# BLE_--_HM-10_--_Carduino_Breakout_v1_0_2.net
KiCad netlist of a schematic drawn in EAGLE
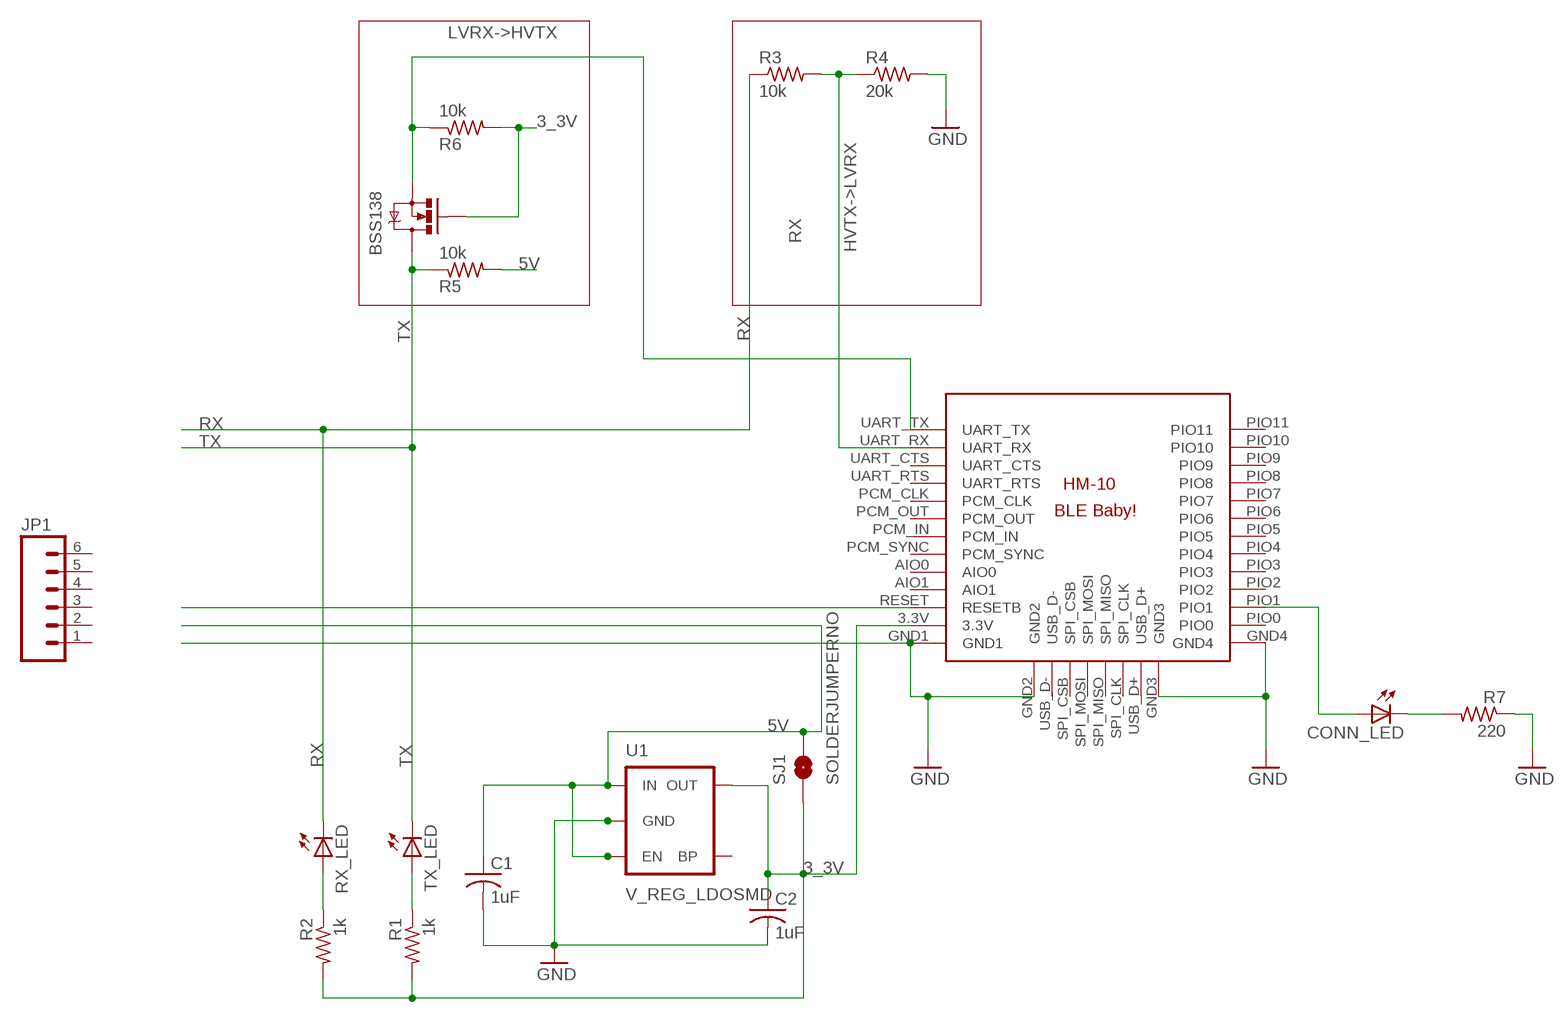
[diagram p0: schematic, sheet 1]

(export (version "E")
  (design (tool "Eeschema 10.0.6"))
  (components
    (comp (ref "BSS138")
      (value "MOSFET-NCHANNELSMD")
      (footprint "eagle-import:SOT23-3")
      (libsource (lib "eagle-import") (part "MOSFET-NCHANNELSMD"))
    )
    (comp (ref "C1")
      (value "1uF")
      (footprint "eagle-import:C0805K")
      (libsource (lib "eagle-import") (part "C-USC0805K"))
    )
    (comp (ref "C2")
      (value "1uF")
      (footprint "eagle-import:C0805K")
      (libsource (lib "eagle-import") (part "C-USC0805K"))
    )
    (comp (ref "CONN_LED")
      (value "LED0603")
      (footprint "eagle-import:LED-0603")
      (libsource (lib "eagle-import") (part "LED0603"))
    )
    (comp (ref "JP1")
      (value "M06SIP")
      (footprint "eagle-import:1X06")
      (libsource (lib "eagle-import") (part "M06SIP"))
    )
    (comp (ref "R1")
      (value "1k")
      (footprint "eagle-import:M0805")
      (libsource (lib "eagle-import") (part "R-US_M0805"))
    )
    (comp (ref "R2")
      (value "1k")
      (footprint "eagle-import:M0805")
      (libsource (lib "eagle-import") (part "R-US_M0805"))
    )
    (comp (ref "R3")
      (value "10k")
      (footprint "eagle-import:M0805")
      (libsource (lib "eagle-import") (part "R-US_M0805"))
    )
    (comp (ref "R4")
      (value "20k")
      (footprint "eagle-import:M0805")
      (libsource (lib "eagle-import") (part "R-US_M0805"))
    )
    (comp (ref "R5")
      (value "10k")
      (footprint "eagle-import:M0805")
      (libsource (lib "eagle-import") (part "R-US_M0805"))
    )
    (comp (ref "R6")
      (value "10k")
      (footprint "eagle-import:M0805")
      (libsource (lib "eagle-import") (part "R-US_M0805"))
    )
    (comp (ref "R7")
      (value "220")
      (footprint "eagle-import:M0805")
      (libsource (lib "eagle-import") (part "R-US_M0805"))
    )
    (comp (ref "RX_LED")
      (value "LED0603")
      (footprint "eagle-import:LED-0603")
      (libsource (lib "eagle-import") (part "LED0603"))
    )
    (comp (ref "SJ1")
      (value "SOLDERJUMPERNO")
      (footprint "eagle-import:SJ_2S-NO")
      (libsource (lib "eagle-import") (part "SOLDERJUMPERNO"))
    )
    (comp (ref "TX_LED")
      (value "LED0603")
      (footprint "eagle-import:LED-0603")
      (libsource (lib "eagle-import") (part "LED0603"))
    )
    (comp (ref "U$1")
      (value "BLE-HM-10")
      (footprint "eagle-import:BLE-HM-10")
      (libsource (lib "eagle-import") (part "BLE-HM-10"))
    )
    (comp (ref "U1")
      (value "V_REG_LDOSMD")
      (footprint "eagle-import:SOT23-5")
      (libsource (lib "eagle-import") (part "V_REG_LDOSMD"))
    )
  )
  (nets
    (net (code "1") (name "/3_3V") (class "Default")
      (node (ref "BSS138") (pin "1") (pinfunction "G_1") (pintype "passive"))
      (node (ref "C2") (pin "1") (pinfunction "1_1") (pintype "passive"))
      (node (ref "R1") (pin "2") (pinfunction "2_2") (pintype "passive"))
      (node (ref "R2") (pin "2") (pinfunction "2_2") (pintype "passive"))
      (node (ref "R6") (pin "2") (pinfunction "2_2") (pintype "passive"))
      (node (ref "SJ1") (pin "1") (pinfunction "1_1") (pintype "passive"))
      (node (ref "U$1") (pin "3.3V") (pinfunction "3.3V_3.3V") (pintype "bidirectional"))
      (node (ref "U1") (pin "5") (pinfunction "OUT_5") (pintype "passive"))
    )
    (net (code "2") (name "/5V") (class "Default")
      (node (ref "C1") (pin "1") (pinfunction "1_1") (pintype "passive"))
      (node (ref "R5") (pin "2") (pinfunction "2_2") (pintype "passive"))
      (node (ref "SJ1") (pin "2") (pinfunction "2_2") (pintype "passive"))
      (node (ref "U1") (pin "1") (pinfunction "IN_1") (pintype "input"))
      (node (ref "U1") (pin "3") (pinfunction "EN_3") (pintype "input"))
    )
    (net (code "3") (name "/HVTX->LVRX") (class "Default")
      (node (ref "R3") (pin "2") (pinfunction "2_2") (pintype "passive"))
      (node (ref "R4") (pin "1") (pinfunction "1_1") (pintype "passive"))
      (node (ref "U$1") (pin "UART_RX") (pinfunction "UART_RX_UART_RX") (pintype "bidirectional"))
    )
    (net (code "4") (name "/LVRX->HVTX") (class "Default")
      (node (ref "BSS138") (pin "2") (pinfunction "S_2") (pintype "passive"))
      (node (ref "R6") (pin "1") (pinfunction "1_1") (pintype "passive"))
      (node (ref "U$1") (pin "UART_TX") (pinfunction "UART_TX_UART_TX") (pintype "bidirectional"))
    )
    (net (code "5") (name "/RX") (class "Default")
      (node (ref "R3") (pin "1") (pinfunction "1_1") (pintype "passive"))
      (node (ref "RX_LED") (pin "C") (pinfunction "C_C") (pintype "passive"))
    )
    (net (code "6") (name "/TX") (class "Default")
      (node (ref "BSS138") (pin "3") (pinfunction "D_3") (pintype "passive"))
      (node (ref "R5") (pin "1") (pinfunction "1_1") (pintype "passive"))
      (node (ref "TX_LED") (pin "C") (pinfunction "C_C") (pintype "passive"))
    )
    (net (code "7") (name "GND") (class "Default")
      (node (ref "C1") (pin "2") (pinfunction "2_2") (pintype "passive"))
      (node (ref "C2") (pin "2") (pinfunction "2_2") (pintype "passive"))
      (node (ref "R4") (pin "2") (pinfunction "2_2") (pintype "passive"))
      (node (ref "R7") (pin "1") (pinfunction "1_1") (pintype "passive"))
      (node (ref "U$1") (pin "GND1") (pinfunction "GND1_GND1") (pintype "bidirectional"))
      (node (ref "U$1") (pin "GND2") (pinfunction "GND2_GND2") (pintype "bidirectional"))
      (node (ref "U$1") (pin "GND3") (pinfunction "GND3_GND3") (pintype "bidirectional"))
      (node (ref "U$1") (pin "GND4") (pinfunction "GND4_GND4") (pintype "bidirectional"))
      (node (ref "U1") (pin "2") (pinfunction "GND_2") (pintype "input"))
    )
    (net (code "8") (name "Net-(CONN_LED-PadA)") (class "Default")
      (node (ref "CONN_LED") (pin "A") (pinfunction "A_A") (pintype "passive"))
      (node (ref "U$1") (pin "PIO1") (pinfunction "PIO1_PIO1") (pintype "bidirectional"))
    )
    (net (code "9") (name "Net-(CONN_LED-PadC)") (class "Default")
      (node (ref "CONN_LED") (pin "C") (pinfunction "C_C") (pintype "passive"))
      (node (ref "R7") (pin "2") (pinfunction "2_2") (pintype "passive"))
    )
    (net (code "10") (name "Net-(R1-Pad1)") (class "Default")
      (node (ref "R1") (pin "1") (pinfunction "1_1") (pintype "passive"))
      (node (ref "TX_LED") (pin "A") (pinfunction "A_A") (pintype "passive"))
    )
    (net (code "11") (name "Net-(R2-Pad1)") (class "Default")
      (node (ref "R2") (pin "1") (pinfunction "1_1") (pintype "passive"))
      (node (ref "RX_LED") (pin "A") (pinfunction "A_A") (pintype "passive"))
    )
    (net (code "12") (name "unconnected-(JP1-Pad1)") (class "Default")
      (node (ref "JP1") (pin "1") (pinfunction "1_1") (pintype "passive"))
    )
    (net (code "13") (name "unconnected-(JP1-Pad2)") (class "Default")
      (node (ref "JP1") (pin "2") (pinfunction "2_2") (pintype "passive"))
    )
    (net (code "14") (name "unconnected-(JP1-Pad3)") (class "Default")
      (node (ref "JP1") (pin "3") (pinfunction "3_3") (pintype "passive"))
    )
    (net (code "15") (name "unconnected-(JP1-Pad4)") (class "Default")
      (node (ref "JP1") (pin "4") (pinfunction "4_4") (pintype "passive"))
    )
    (net (code "16") (name "unconnected-(JP1-Pad5)") (class "Default")
      (node (ref "JP1") (pin "5") (pinfunction "5_5") (pintype "passive"))
    )
    (net (code "17") (name "unconnected-(JP1-Pad6)") (class "Default")
      (node (ref "JP1") (pin "6") (pinfunction "6_6") (pintype "passive"))
    )
    (net (code "18") (name "unconnected-(U$1-PadAIO0)") (class "Default")
      (node (ref "U$1") (pin "AIO0") (pinfunction "AIO0_AIO0") (pintype "bidirectional"))
    )
    (net (code "19") (name "unconnected-(U$1-PadAIO1)") (class "Default")
      (node (ref "U$1") (pin "AIO1") (pinfunction "AIO1_AIO1") (pintype "bidirectional"))
    )
    (net (code "20") (name "unconnected-(U$1-PadPCM_CLK)") (class "Default")
      (node (ref "U$1") (pin "PCM_CLK") (pinfunction "PCM_CLK_PCM_CLK") (pintype "bidirectional"))
    )
    (net (code "21") (name "unconnected-(U$1-PadPCM_IN)") (class "Default")
      (node (ref "U$1") (pin "PCM_IN") (pinfunction "PCM_IN_PCM_IN") (pintype "bidirectional"))
    )
    (net (code "22") (name "unconnected-(U$1-PadPCM_OUT)") (class "Default")
      (node (ref "U$1") (pin "PCM_OUT") (pinfunction "PCM_OUT_PCM_OUT") (pintype "bidirectional"))
    )
    (net (code "23") (name "unconnected-(U$1-PadPCM_SYNC)") (class "Default")
      (node (ref "U$1") (pin "PCM_SYNC") (pinfunction "PCM_SYNC_PCM_SYNC") (pintype "bidirectional"))
    )
    (net (code "24") (name "unconnected-(U$1-PadPIO0)") (class "Default")
      (node (ref "U$1") (pin "PIO0") (pinfunction "PIO0_PIO0") (pintype "bidirectional"))
    )
    (net (code "25") (name "unconnected-(U$1-PadPIO2)") (class "Default")
      (node (ref "U$1") (pin "PIO2") (pinfunction "PIO2_PIO2") (pintype "bidirectional"))
    )
    (net (code "26") (name "unconnected-(U$1-PadPIO3)") (class "Default")
      (node (ref "U$1") (pin "PIO3") (pinfunction "PIO3_PIO3") (pintype "bidirectional"))
    )
    (net (code "27") (name "unconnected-(U$1-PadPIO4)") (class "Default")
      (node (ref "U$1") (pin "PIO4") (pinfunction "PIO4_PIO4") (pintype "bidirectional"))
    )
    (net (code "28") (name "unconnected-(U$1-PadPIO5)") (class "Default")
      (node (ref "U$1") (pin "PIO5") (pinfunction "PIO5_PIO5") (pintype "bidirectional"))
    )
    (net (code "29") (name "unconnected-(U$1-PadPIO6)") (class "Default")
      (node (ref "U$1") (pin "PIO6") (pinfunction "PIO6_PIO6") (pintype "bidirectional"))
    )
    (net (code "30") (name "unconnected-(U$1-PadPIO7)") (class "Default")
      (node (ref "U$1") (pin "PIO7") (pinfunction "PIO7_PIO7") (pintype "bidirectional"))
    )
    (net (code "31") (name "unconnected-(U$1-PadPIO8)") (class "Default")
      (node (ref "U$1") (pin "PIO8") (pinfunction "PIO8_PIO8") (pintype "bidirectional"))
    )
    (net (code "32") (name "unconnected-(U$1-PadPIO9)") (class "Default")
      (node (ref "U$1") (pin "PIO9") (pinfunction "PIO9_PIO9") (pintype "bidirectional"))
    )
    (net (code "33") (name "unconnected-(U$1-PadPIO10)") (class "Default")
      (node (ref "U$1") (pin "PIO10") (pinfunction "PIO10_PIO10") (pintype "bidirectional"))
    )
    (net (code "34") (name "unconnected-(U$1-PadPIO11)") (class "Default")
      (node (ref "U$1") (pin "PIO11") (pinfunction "PIO11_PIO11") (pintype "bidirectional"))
    )
    (net (code "35") (name "unconnected-(U$1-PadSPI_CLK)") (class "Default")
      (node (ref "U$1") (pin "SPI_CLK") (pinfunction "SPI_CLK_SPI_CLK") (pintype "bidirectional"))
    )
    (net (code "36") (name "unconnected-(U$1-PadSPI_CSB)") (class "Default")
      (node (ref "U$1") (pin "SPI_CSB") (pinfunction "SPI_CSB_SPI_CSB") (pintype "bidirectional"))
    )
    (net (code "37") (name "unconnected-(U$1-PadSPI_MISO)") (class "Default")
      (node (ref "U$1") (pin "SPI_MISO") (pinfunction "SPI_MISO_SPI_MISO") (pintype "bidirectional"))
    )
    (net (code "38") (name "unconnected-(U$1-PadSPI_MOSI)") (class "Default")
      (node (ref "U$1") (pin "SPI_MOSI") (pinfunction "SPI_MOSI_SPI_MOSI") (pintype "bidirectional"))
    )
    (net (code "39") (name "unconnected-(U$1-PadUART_CTS)") (class "Default")
      (node (ref "U$1") (pin "UART_CTS") (pinfunction "UART_CTS_UART_CTS") (pintype "bidirectional"))
    )
    (net (code "40") (name "unconnected-(U$1-PadUART_RTS)") (class "Default")
      (node (ref "U$1") (pin "UART_RTS") (pinfunction "UART_RTS_UART_RTS") (pintype "bidirectional"))
    )
    (net (code "41") (name "unconnected-(U$1-PadUSB_D+)") (class "Default")
      (node (ref "U$1") (pin "USB_D+") (pinfunction "USB_D+_USB_D+") (pintype "bidirectional"))
    )
    (net (code "42") (name "unconnected-(U$1-PadUSB_D-)") (class "Default")
      (node (ref "U$1") (pin "USB_D-") (pinfunction "USB_D-_USB_D-") (pintype "bidirectional"))
    )
    (net (code "43") (name "unconnected-(U$1-RESETB-PadRESET)") (class "Default")
      (node (ref "U$1") (pin "RESET") (pinfunction "RESETB_RESET") (pintype "bidirectional"))
    )
    (net (code "44") (name "unconnected-(U1-BP-Pad4)") (class "Default")
      (node (ref "U1") (pin "4") (pinfunction "BP_4") (pintype "input"))
    )
  )
)
